# Peak_Detector.net
KiCad netlist of a schematic drawn in Altium Designer
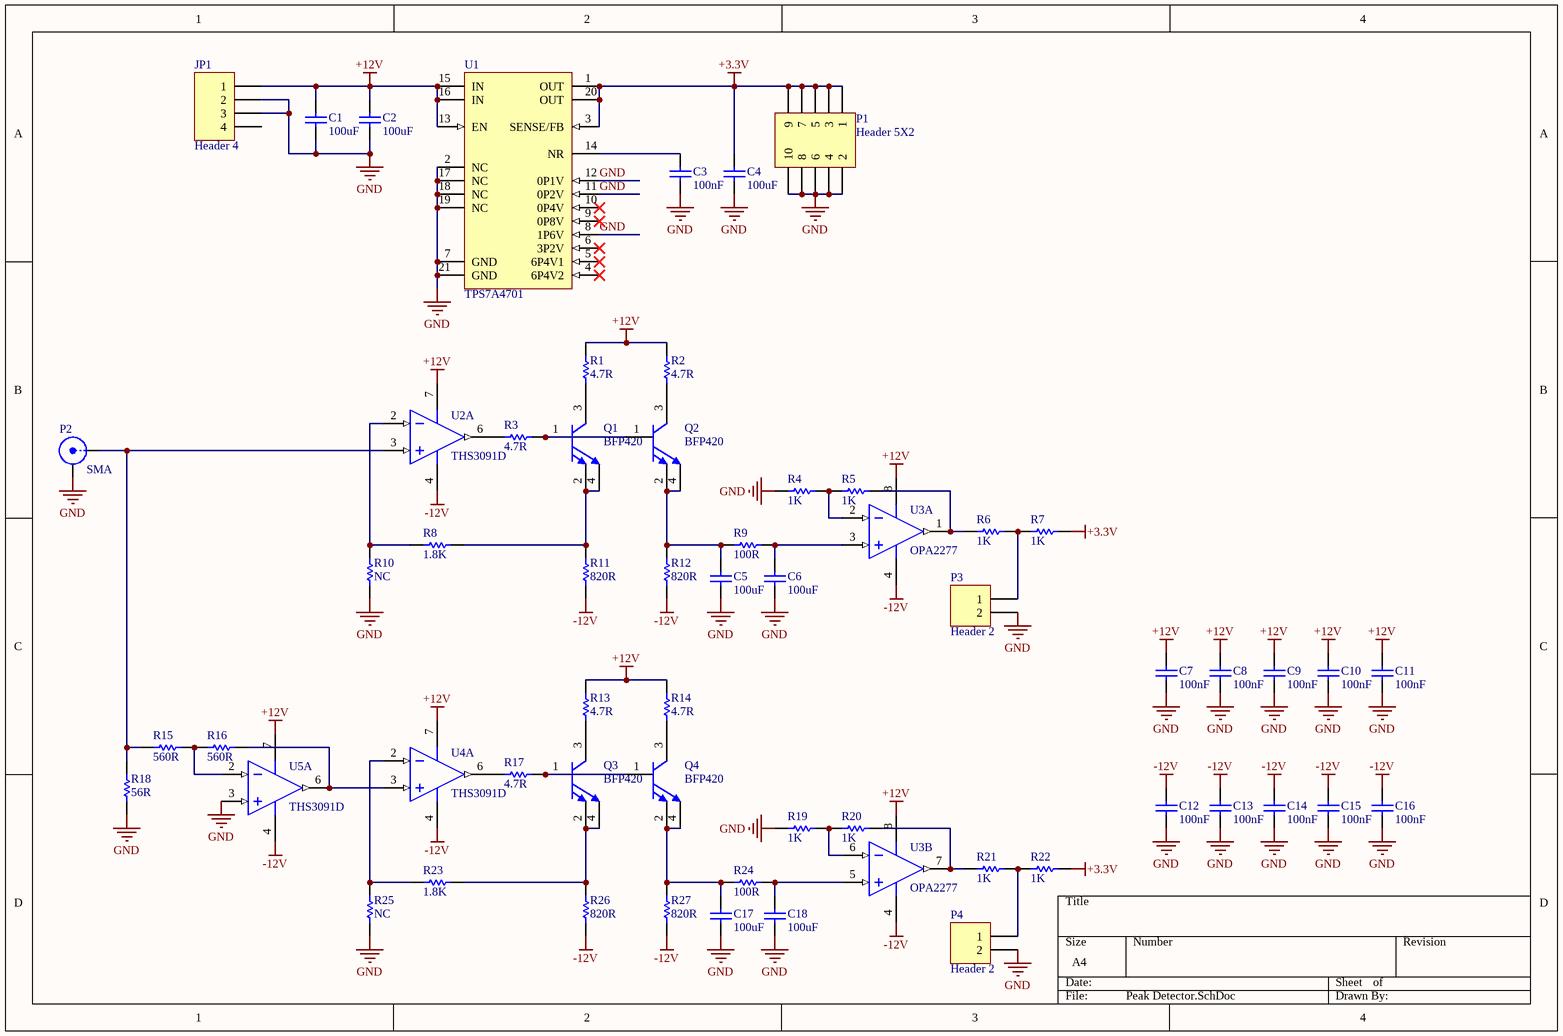
[diagram p0: Peak Detector.SchDoc]

(export (version "E")
  (design (tool "Eeschema 10.0.6"))
  (components
    (comp (ref "C1") (value "100uF") (footprint "CAPC3225") (libsource (lib "Slivy's Library") (part "CAP")))
    (comp (ref "C2") (value "100uF") (footprint "CAPC3225") (libsource (lib "Slivy's Library") (part "CAP")))
    (comp (ref "C3")
      (value "100nF")
      (footprint "CAPC0603(1608)55_M")
      (libsource (lib "Slivy's Library") (part "CAP"))
    )
    (comp (ref "C4") (value "100uF") (footprint "CAPC3225") (libsource (lib "Slivy's Library") (part "CAP")))
    (comp (ref "C5") (value "100uF") (footprint "CAPC3225") (libsource (lib "Slivy's Library") (part "CAP")))
    (comp (ref "C6") (value "100uF") (footprint "CAPC3225") (libsource (lib "Slivy's Library") (part "CAP")))
    (comp (ref "C7")
      (value "100nF")
      (footprint "CAPC0603(1608)55_M")
      (libsource (lib "Slivy's Library") (part "CAP"))
    )
    (comp (ref "C8")
      (value "100nF")
      (footprint "CAPC0603(1608)55_M")
      (libsource (lib "Slivy's Library") (part "CAP"))
    )
    (comp (ref "C9")
      (value "100nF")
      (footprint "CAPC0603(1608)55_M")
      (libsource (lib "Slivy's Library") (part "CAP"))
    )
    (comp (ref "C10")
      (value "100nF")
      (footprint "CAPC0603(1608)55_M")
      (libsource (lib "Slivy's Library") (part "CAP"))
    )
    (comp (ref "C11")
      (value "100nF")
      (footprint "CAPC0603(1608)55_M")
      (libsource (lib "Slivy's Library") (part "CAP"))
    )
    (comp (ref "C12")
      (value "100nF")
      (footprint "CAPC0603(1608)55_M")
      (libsource (lib "Slivy's Library") (part "CAP"))
    )
    (comp (ref "C13")
      (value "100nF")
      (footprint "CAPC0603(1608)55_M")
      (libsource (lib "Slivy's Library") (part "CAP"))
    )
    (comp (ref "C14")
      (value "100nF")
      (footprint "CAPC0603(1608)55_M")
      (libsource (lib "Slivy's Library") (part "CAP"))
    )
    (comp (ref "C15")
      (value "100nF")
      (footprint "CAPC0603(1608)55_M")
      (libsource (lib "Slivy's Library") (part "CAP"))
    )
    (comp (ref "C16")
      (value "100nF")
      (footprint "CAPC0603(1608)55_M")
      (libsource (lib "Slivy's Library") (part "CAP"))
    )
    (comp (ref "C17") (value "100uF") (footprint "CAPC3225") (libsource (lib "Slivy's Library") (part "CAP")))
    (comp (ref "C18") (value "100uF") (footprint "CAPC3225") (libsource (lib "Slivy's Library") (part "CAP")))
    (comp (ref "JP1")
      (value "Header 4")
      (footprint "3.96-4")
      (description "Header, 4-Pin")
      (fields (field (name "MANUFACTURER") "Generic Components"))
      (libsource (lib "Integrated_Library1") (part "Header 4"))
    )
    (comp (ref "P1")
      (value "Header 5X2")
      (footprint "HDR2X5")
      (description "Header, 5-Pin, Dual row")
      (fields (field (name "PUBLISHER") "Altium Limited"))
      (libsource (lib "Miscellaneous Connectors") (part "Header 5X2"))
    )
    (comp (ref "P2")
      (value "SMA")
      (footprint "SMA-V")
      (fields (field (name "PUBLISHER") "Altium Limited"))
      (libsource (lib "Slivy's Library") (part "SMA"))
    )
    (comp (ref "P3")
      (value "Header 2")
      (footprint "HDR1X2")
      (description "Header, 2-Pin")
      (fields (field (name "PUBLISHER") "Altium Limited"))
      (libsource (lib "Miscellaneous Connectors") (part "Header 2"))
    )
    (comp (ref "P4")
      (value "Header 2")
      (footprint "HDR1X2")
      (description "Header, 2-Pin")
      (fields (field (name "PUBLISHER") "Altium Limited"))
      (libsource (lib "Miscellaneous Connectors") (part "Header 2"))
    )
    (comp (ref "Q1")
      (value "BFP420")
      (footprint "SOT343")
      (libsource (lib "Slivy's Library") (part "BFP420"))
    )
    (comp (ref "Q2")
      (value "BFP420")
      (footprint "SOT343")
      (libsource (lib "Slivy's Library") (part "BFP420"))
    )
    (comp (ref "Q3")
      (value "BFP420")
      (footprint "SOT343")
      (libsource (lib "Slivy's Library") (part "BFP420"))
    )
    (comp (ref "Q4")
      (value "BFP420")
      (footprint "SOT343")
      (libsource (lib "Slivy's Library") (part "BFP420"))
    )
    (comp (ref "R1")
      (value "4.7R")
      (footprint "RESC0603(1608)_M")
      (libsource (lib "Slivy's Library") (part "RES"))
    )
    (comp (ref "R2")
      (value "4.7R")
      (footprint "RESC0603(1608)_M")
      (libsource (lib "Slivy's Library") (part "RES"))
    )
    (comp (ref "R3")
      (value "4.7R")
      (footprint "RESC0603(1608)_M")
      (libsource (lib "Slivy's Library") (part "RES"))
    )
    (comp (ref "R4")
      (value "1K")
      (footprint "RESC0603(1608)_M")
      (libsource (lib "Slivy's Library") (part "RES"))
    )
    (comp (ref "R5")
      (value "1K")
      (footprint "RESC0603(1608)_M")
      (libsource (lib "Slivy's Library") (part "RES"))
    )
    (comp (ref "R6")
      (value "1K")
      (footprint "RESC0603(1608)_M")
      (libsource (lib "Slivy's Library") (part "RES"))
    )
    (comp (ref "R7")
      (value "1K")
      (footprint "RESC0603(1608)_M")
      (libsource (lib "Slivy's Library") (part "RES"))
    )
    (comp (ref "R8")
      (value "1.8K")
      (footprint "RESC0603(1608)_M")
      (libsource (lib "Slivy's Library") (part "RES"))
    )
    (comp (ref "R9")
      (value "100R")
      (footprint "RESC0603(1608)_M")
      (libsource (lib "Slivy's Library") (part "RES"))
    )
    (comp (ref "R10")
      (value "NC")
      (footprint "RESC0603(1608)_M")
      (libsource (lib "Slivy's Library") (part "RES"))
    )
    (comp (ref "R11")
      (value "820R")
      (footprint "RESC0603(1608)_M")
      (libsource (lib "Slivy's Library") (part "RES"))
    )
    (comp (ref "R12")
      (value "820R")
      (footprint "RESC0603(1608)_M")
      (libsource (lib "Slivy's Library") (part "RES"))
    )
    (comp (ref "R13")
      (value "4.7R")
      (footprint "RESC0603(1608)_M")
      (libsource (lib "Slivy's Library") (part "RES"))
    )
    (comp (ref "R14")
      (value "4.7R")
      (footprint "RESC0603(1608)_M")
      (libsource (lib "Slivy's Library") (part "RES"))
    )
    (comp (ref "R15")
      (value "560R")
      (footprint "RESC0603(1608)_M")
      (libsource (lib "Slivy's Library") (part "RES"))
    )
    (comp (ref "R16")
      (value "560R")
      (footprint "RESC0603(1608)_M")
      (libsource (lib "Slivy's Library") (part "RES"))
    )
    (comp (ref "R17")
      (value "4.7R")
      (footprint "RESC0603(1608)_M")
      (libsource (lib "Slivy's Library") (part "RES"))
    )
    (comp (ref "R18")
      (value "56R")
      (footprint "RESC0603(1608)_M")
      (libsource (lib "Slivy's Library") (part "RES"))
    )
    (comp (ref "R19")
      (value "1K")
      (footprint "RESC0603(1608)_M")
      (libsource (lib "Slivy's Library") (part "RES"))
    )
    (comp (ref "R20")
      (value "1K")
      (footprint "RESC0603(1608)_M")
      (libsource (lib "Slivy's Library") (part "RES"))
    )
    (comp (ref "R21")
      (value "1K")
      (footprint "RESC0603(1608)_M")
      (libsource (lib "Slivy's Library") (part "RES"))
    )
    (comp (ref "R22")
      (value "1K")
      (footprint "RESC0603(1608)_M")
      (libsource (lib "Slivy's Library") (part "RES"))
    )
    (comp (ref "R23")
      (value "1.8K")
      (footprint "RESC0603(1608)_M")
      (libsource (lib "Slivy's Library") (part "RES"))
    )
    (comp (ref "R24")
      (value "100R")
      (footprint "RESC0603(1608)_M")
      (libsource (lib "Slivy's Library") (part "RES"))
    )
    (comp (ref "R25")
      (value "NC")
      (footprint "RESC0603(1608)_M")
      (libsource (lib "Slivy's Library") (part "RES"))
    )
    (comp (ref "R26")
      (value "820R")
      (footprint "RESC0603(1608)_M")
      (libsource (lib "Slivy's Library") (part "RES"))
    )
    (comp (ref "R27")
      (value "820R")
      (footprint "RESC0603(1608)_M")
      (libsource (lib "Slivy's Library") (part "RES"))
    )
    (comp (ref "U1")
      (value "TPS7A4701")
      (footprint "QFN20")
      (libsource (lib "Slivy's Library") (part "TPS7A4701"))
    )
    (comp (ref "U2")
      (value "THS3091D")
      (footprint "SOIC8")
      (libsource (lib "Slivy's Library") (part "THS3201"))
    )
    (comp (ref "U3") (value "OPA2277") (footprint "SOIC8") (libsource (lib "Slivy's Library") (part "OP2")))
    (comp (ref "U4")
      (value "THS3091D")
      (footprint "SOIC8")
      (libsource (lib "Slivy's Library") (part "THS3201"))
    )
    (comp (ref "U5")
      (value "THS3091D")
      (footprint "SOIC8")
      (libsource (lib "Slivy's Library") (part "THS3201"))
    )
  )
  (nets
    (net (code "1") (name "+3.3V") (class "Default")
      (node (ref "C4") (pin "2") (pinfunction "2_2") (pintype "passive"))
      (node (ref "P1") (pin "1") (pinfunction "1_1") (pintype "passive"))
      (node (ref "P1") (pin "3") (pinfunction "3_3") (pintype "passive"))
      (node (ref "P1") (pin "5") (pinfunction "5_5") (pintype "passive"))
      (node (ref "P1") (pin "7") (pinfunction "7_7") (pintype "passive"))
      (node (ref "P1") (pin "9") (pinfunction "9_9") (pintype "passive"))
      (node (ref "R22") (pin "1") (pinfunction "1_1") (pintype "passive"))
      (node (ref "R7") (pin "1") (pinfunction "1_1") (pintype "passive"))
      (node (ref "U1") (pin "1") (pinfunction "OUT_1") (pintype "power_in"))
      (node (ref "U1") (pin "20") (pinfunction "OUT_20") (pintype "power_in"))
      (node (ref "U1") (pin "3") (pinfunction "SENSE/FB_3") (pintype "input"))
    )
    (net (code "2") (name "+12V") (class "Default")
      (node (ref "C1") (pin "2") (pinfunction "2_2") (pintype "passive"))
      (node (ref "C10") (pin "2") (pinfunction "2_2") (pintype "passive"))
      (node (ref "C11") (pin "2") (pinfunction "2_2") (pintype "passive"))
      (node (ref "C2") (pin "2") (pinfunction "2_2") (pintype "passive"))
      (node (ref "C7") (pin "2") (pinfunction "2_2") (pintype "passive"))
      (node (ref "C8") (pin "2") (pinfunction "2_2") (pintype "passive"))
      (node (ref "C9") (pin "2") (pinfunction "2_2") (pintype "passive"))
      (node (ref "JP1") (pin "1") (pinfunction "1_1") (pintype "passive"))
      (node (ref "R1") (pin "2") (pinfunction "2_2") (pintype "passive"))
      (node (ref "R13") (pin "2") (pinfunction "2_2") (pintype "passive"))
      (node (ref "R14") (pin "2") (pinfunction "2_2") (pintype "passive"))
      (node (ref "R2") (pin "2") (pinfunction "2_2") (pintype "passive"))
      (node (ref "U1") (pin "13") (pinfunction "EN_13") (pintype "input"))
      (node (ref "U1") (pin "15") (pinfunction "IN_15") (pintype "power_in"))
      (node (ref "U1") (pin "16") (pinfunction "IN_16") (pintype "power_in"))
      (node (ref "U2") (pin "7") (pinfunction "VS+_7") (pintype "power_in"))
      (node (ref "U3") (pin "8") (pinfunction "V+_8") (pintype "power_in"))
      (node (ref "U4") (pin "7") (pinfunction "VS+_7") (pintype "power_in"))
      (node (ref "U5") (pin "7") (pinfunction "VS+_7") (pintype "power_in"))
    )
    (net (code "3") (name "-12V") (class "Default")
      (node (ref "C12") (pin "2") (pinfunction "2_2") (pintype "passive"))
      (node (ref "C13") (pin "2") (pinfunction "2_2") (pintype "passive"))
      (node (ref "C14") (pin "2") (pinfunction "2_2") (pintype "passive"))
      (node (ref "C15") (pin "2") (pinfunction "2_2") (pintype "passive"))
      (node (ref "C16") (pin "2") (pinfunction "2_2") (pintype "passive"))
      (node (ref "R11") (pin "1") (pinfunction "1_1") (pintype "passive"))
      (node (ref "R12") (pin "1") (pinfunction "1_1") (pintype "passive"))
      (node (ref "R26") (pin "1") (pinfunction "1_1") (pintype "passive"))
      (node (ref "R27") (pin "1") (pinfunction "1_1") (pintype "passive"))
      (node (ref "U2") (pin "4") (pinfunction "VS-_4") (pintype "power_in"))
      (node (ref "U3") (pin "4") (pinfunction "V-_4") (pintype "power_in"))
      (node (ref "U4") (pin "4") (pinfunction "VS-_4") (pintype "power_in"))
      (node (ref "U5") (pin "4") (pinfunction "VS-_4") (pintype "power_in"))
    )
    (net (code "4") (name "GND") (class "Default")
      (node (ref "C1") (pin "1") (pinfunction "1_1") (pintype "passive"))
      (node (ref "C10") (pin "1") (pinfunction "1_1") (pintype "passive"))
      (node (ref "C11") (pin "1") (pinfunction "1_1") (pintype "passive"))
      (node (ref "C12") (pin "1") (pinfunction "1_1") (pintype "passive"))
      (node (ref "C13") (pin "1") (pinfunction "1_1") (pintype "passive"))
      (node (ref "C14") (pin "1") (pinfunction "1_1") (pintype "passive"))
      (node (ref "C15") (pin "1") (pinfunction "1_1") (pintype "passive"))
      (node (ref "C16") (pin "1") (pinfunction "1_1") (pintype "passive"))
      (node (ref "C17") (pin "1") (pinfunction "1_1") (pintype "passive"))
      (node (ref "C18") (pin "1") (pinfunction "1_1") (pintype "passive"))
      (node (ref "C2") (pin "1") (pinfunction "1_1") (pintype "passive"))
      (node (ref "C3") (pin "1") (pinfunction "1_1") (pintype "passive"))
      (node (ref "C4") (pin "1") (pinfunction "1_1") (pintype "passive"))
      (node (ref "C5") (pin "1") (pinfunction "1_1") (pintype "passive"))
      (node (ref "C6") (pin "1") (pinfunction "1_1") (pintype "passive"))
      (node (ref "C7") (pin "1") (pinfunction "1_1") (pintype "passive"))
      (node (ref "C8") (pin "1") (pinfunction "1_1") (pintype "passive"))
      (node (ref "C9") (pin "1") (pinfunction "1_1") (pintype "passive"))
      (node (ref "JP1") (pin "2") (pinfunction "2_2") (pintype "passive"))
      (node (ref "JP1") (pin "3") (pinfunction "3_3") (pintype "passive"))
      (node (ref "P1") (pin "10") (pinfunction "10_10") (pintype "passive"))
      (node (ref "P1") (pin "2") (pinfunction "2_2") (pintype "passive"))
      (node (ref "P1") (pin "4") (pinfunction "4_4") (pintype "passive"))
      (node (ref "P1") (pin "6") (pinfunction "6_6") (pintype "passive"))
      (node (ref "P1") (pin "8") (pinfunction "8_8") (pintype "passive"))
      (node (ref "P2") (pin "2") (pinfunction "Y_2") (pintype "passive"))
      (node (ref "P3") (pin "2") (pinfunction "2_2") (pintype "passive"))
      (node (ref "P4") (pin "2") (pinfunction "2_2") (pintype "passive"))
      (node (ref "R10") (pin "2") (pinfunction "2_2") (pintype "passive"))
      (node (ref "R18") (pin "2") (pinfunction "2_2") (pintype "passive"))
      (node (ref "R19") (pin "2") (pinfunction "2_2") (pintype "passive"))
      (node (ref "R25") (pin "2") (pinfunction "2_2") (pintype "passive"))
      (node (ref "R4") (pin "2") (pinfunction "2_2") (pintype "passive"))
      (node (ref "U1") (pin "11") (pinfunction "0P2V_11") (pintype "input"))
      (node (ref "U1") (pin "12") (pinfunction "0P1V_12") (pintype "input"))
      (node (ref "U1") (pin "17") (pinfunction "NC_17") (pintype "passive"))
      (node (ref "U1") (pin "18") (pinfunction "NC_18") (pintype "passive"))
      (node (ref "U1") (pin "19") (pinfunction "NC_19") (pintype "passive"))
      (node (ref "U1") (pin "2") (pinfunction "NC_2") (pintype "passive"))
      (node (ref "U1") (pin "21") (pinfunction "GND_21") (pintype "power_in"))
      (node (ref "U1") (pin "7") (pinfunction "GND_7") (pintype "power_in"))
      (node (ref "U1") (pin "8") (pinfunction "1P6V_8") (pintype "input"))
      (node (ref "U5") (pin "3") (pinfunction "VIN+_3") (pintype "input"))
    )
    (net (code "5") (name "Net-(C5-Pad2)") (class "Default")
      (node (ref "C5") (pin "2") (pinfunction "2_2") (pintype "passive"))
      (node (ref "Q2") (pin "2") (pinfunction "E_2") (pintype "passive"))
      (node (ref "Q2") (pin "4") (pinfunction "E_4") (pintype "passive"))
      (node (ref "R12") (pin "2") (pinfunction "2_2") (pintype "passive"))
      (node (ref "R9") (pin "2") (pinfunction "2_2") (pintype "passive"))
    )
    (net (code "6") (name "Net-(C17-Pad2)") (class "Default")
      (node (ref "C17") (pin "2") (pinfunction "2_2") (pintype "passive"))
      (node (ref "Q4") (pin "2") (pinfunction "E_2") (pintype "passive"))
      (node (ref "Q4") (pin "4") (pinfunction "E_4") (pintype "passive"))
      (node (ref "R24") (pin "2") (pinfunction "2_2") (pintype "passive"))
      (node (ref "R27") (pin "2") (pinfunction "2_2") (pintype "passive"))
    )
    (net (code "7") (name "Net-(P2-X)") (class "Default")
      (node (ref "P2") (pin "1") (pinfunction "X_1") (pintype "passive"))
      (node (ref "R15") (pin "2") (pinfunction "2_2") (pintype "passive"))
      (node (ref "R18") (pin "1") (pinfunction "1_1") (pintype "passive"))
      (node (ref "U2") (pin "3") (pinfunction "VIN+_3") (pintype "input"))
    )
    (net (code "8") (name "Net-(P3-Pad1)") (class "Default")
      (node (ref "P3") (pin "1") (pinfunction "1_1") (pintype "passive"))
      (node (ref "R6") (pin "1") (pinfunction "1_1") (pintype "passive"))
      (node (ref "R7") (pin "2") (pinfunction "2_2") (pintype "passive"))
    )
    (net (code "9") (name "Net-(P4-Pad1)") (class "Default")
      (node (ref "P4") (pin "1") (pinfunction "1_1") (pintype "passive"))
      (node (ref "R21") (pin "1") (pinfunction "1_1") (pintype "passive"))
      (node (ref "R22") (pin "2") (pinfunction "2_2") (pintype "passive"))
    )
    (net (code "10") (name "Net-(Q1-B)") (class "Default")
      (node (ref "Q1") (pin "1") (pinfunction "B_1") (pintype "passive"))
      (node (ref "Q2") (pin "1") (pinfunction "B_1") (pintype "passive"))
      (node (ref "R3") (pin "1") (pinfunction "1_1") (pintype "passive"))
    )
    (net (code "11") (name "Net-(Q1-C)") (class "Default")
      (node (ref "Q1") (pin "3") (pinfunction "C_3") (pintype "passive"))
      (node (ref "R1") (pin "1") (pinfunction "1_1") (pintype "passive"))
    )
    (net (code "12") (name "Net-(Q1-E-Pad2)") (class "Default")
      (node (ref "Q1") (pin "2") (pinfunction "E_2") (pintype "passive"))
      (node (ref "Q1") (pin "4") (pinfunction "E_4") (pintype "passive"))
      (node (ref "R11") (pin "2") (pinfunction "2_2") (pintype "passive"))
      (node (ref "R8") (pin "1") (pinfunction "1_1") (pintype "passive"))
    )
    (net (code "13") (name "Net-(Q2-C)") (class "Default")
      (node (ref "Q2") (pin "3") (pinfunction "C_3") (pintype "passive"))
      (node (ref "R2") (pin "1") (pinfunction "1_1") (pintype "passive"))
    )
    (net (code "14") (name "Net-(Q3-B)") (class "Default")
      (node (ref "Q3") (pin "1") (pinfunction "B_1") (pintype "passive"))
      (node (ref "Q4") (pin "1") (pinfunction "B_1") (pintype "passive"))
      (node (ref "R17") (pin "1") (pinfunction "1_1") (pintype "passive"))
    )
    (net (code "15") (name "Net-(Q3-C)") (class "Default")
      (node (ref "Q3") (pin "3") (pinfunction "C_3") (pintype "passive"))
      (node (ref "R13") (pin "1") (pinfunction "1_1") (pintype "passive"))
    )
    (net (code "16") (name "Net-(Q3-E-Pad2)") (class "Default")
      (node (ref "Q3") (pin "2") (pinfunction "E_2") (pintype "passive"))
      (node (ref "Q3") (pin "4") (pinfunction "E_4") (pintype "passive"))
      (node (ref "R23") (pin "1") (pinfunction "1_1") (pintype "passive"))
      (node (ref "R26") (pin "2") (pinfunction "2_2") (pintype "passive"))
    )
    (net (code "17") (name "Net-(Q4-C)") (class "Default")
      (node (ref "Q4") (pin "3") (pinfunction "C_3") (pintype "passive"))
      (node (ref "R14") (pin "1") (pinfunction "1_1") (pintype "passive"))
    )
    (net (code "18") (name "Net-(U1-NR)") (class "Default")
      (node (ref "C3") (pin "2") (pinfunction "2_2") (pintype "passive"))
      (node (ref "U1") (pin "14") (pinfunction "NR_14") (pintype "passive"))
    )
    (net (code "19") (name "Net-(U2A-VIN-)") (class "Default")
      (node (ref "R10") (pin "1") (pinfunction "1_1") (pintype "passive"))
      (node (ref "R8") (pin "2") (pinfunction "2_2") (pintype "passive"))
      (node (ref "U2") (pin "2") (pinfunction "VIN-_2") (pintype "input"))
    )
    (net (code "20") (name "Net-(U2A-VOUT)") (class "Default")
      (node (ref "R3") (pin "2") (pinfunction "2_2") (pintype "passive"))
      (node (ref "U2") (pin "6") (pinfunction "VOUT_6") (pintype "output"))
    )
    (net (code "21") (name "Net-(U3A-IN_A+)") (class "Default")
      (node (ref "C6") (pin "2") (pinfunction "2_2") (pintype "passive"))
      (node (ref "R9") (pin "1") (pinfunction "1_1") (pintype "passive"))
      (node (ref "U3") (pin "3") (pinfunction "IN_A+_3") (pintype "input"))
    )
    (net (code "22") (name "Net-(U3A-IN_A-)") (class "Default")
      (node (ref "R4") (pin "1") (pinfunction "1_1") (pintype "passive"))
      (node (ref "R5") (pin "2") (pinfunction "2_2") (pintype "passive"))
      (node (ref "U3") (pin "2") (pinfunction "IN_A-_2") (pintype "input"))
    )
    (net (code "23") (name "Net-(U3A-OUT_A)") (class "Default")
      (node (ref "R5") (pin "1") (pinfunction "1_1") (pintype "passive"))
      (node (ref "R6") (pin "2") (pinfunction "2_2") (pintype "passive"))
      (node (ref "U3") (pin "1") (pinfunction "OUT_A_1") (pintype "output"))
    )
    (net (code "24") (name "Net-(U3B-IN_B+)") (class "Default")
      (node (ref "C18") (pin "2") (pinfunction "2_2") (pintype "passive"))
      (node (ref "R24") (pin "1") (pinfunction "1_1") (pintype "passive"))
      (node (ref "U3") (pin "5") (pinfunction "IN_B+_5") (pintype "input"))
    )
    (net (code "25") (name "Net-(U3B-IN_B-)") (class "Default")
      (node (ref "R19") (pin "1") (pinfunction "1_1") (pintype "passive"))
      (node (ref "R20") (pin "2") (pinfunction "2_2") (pintype "passive"))
      (node (ref "U3") (pin "6") (pinfunction "IN_B-_6") (pintype "input"))
    )
    (net (code "26") (name "Net-(U3B-OUT_B)") (class "Default")
      (node (ref "R20") (pin "1") (pinfunction "1_1") (pintype "passive"))
      (node (ref "R21") (pin "2") (pinfunction "2_2") (pintype "passive"))
      (node (ref "U3") (pin "7") (pinfunction "OUT_B_7") (pintype "output"))
    )
    (net (code "27") (name "Net-(U4A-VIN+)") (class "Default")
      (node (ref "R16") (pin "1") (pinfunction "1_1") (pintype "passive"))
      (node (ref "U4") (pin "3") (pinfunction "VIN+_3") (pintype "input"))
      (node (ref "U5") (pin "6") (pinfunction "VOUT_6") (pintype "output"))
    )
    (net (code "28") (name "Net-(U4A-VIN-)") (class "Default")
      (node (ref "R23") (pin "2") (pinfunction "2_2") (pintype "passive"))
      (node (ref "R25") (pin "1") (pinfunction "1_1") (pintype "passive"))
      (node (ref "U4") (pin "2") (pinfunction "VIN-_2") (pintype "input"))
    )
    (net (code "29") (name "Net-(U4A-VOUT)") (class "Default")
      (node (ref "R17") (pin "2") (pinfunction "2_2") (pintype "passive"))
      (node (ref "U4") (pin "6") (pinfunction "VOUT_6") (pintype "output"))
    )
    (net (code "30") (name "Net-(U5A-VIN-)") (class "Default")
      (node (ref "R15") (pin "1") (pinfunction "1_1") (pintype "passive"))
      (node (ref "R16") (pin "2") (pinfunction "2_2") (pintype "passive"))
      (node (ref "U5") (pin "2") (pinfunction "VIN-_2") (pintype "input"))
    )
    (net (code "31") (name "unconnected-(JP1-Pad4)") (class "Default")
      (node (ref "JP1") (pin "4") (pinfunction "4_4") (pintype "passive"))
    )
    (net (code "32") (name "unconnected-(U1-0P4V-Pad10)") (class "Default")
      (node (ref "U1") (pin "10") (pinfunction "0P4V_10") (pintype "input+no_connect"))
    )
    (net (code "33") (name "unconnected-(U1-0P8V-Pad9)") (class "Default")
      (node (ref "U1") (pin "9") (pinfunction "0P8V_9") (pintype "input+no_connect"))
    )
    (net (code "34") (name "unconnected-(U1-3P2V-Pad6)") (class "Default")
      (node (ref "U1") (pin "6") (pinfunction "3P2V_6") (pintype "input+no_connect"))
    )
    (net (code "35") (name "unconnected-(U1-6P4V1-Pad5)") (class "Default")
      (node (ref "U1") (pin "5") (pinfunction "6P4V1_5") (pintype "input+no_connect"))
    )
    (net (code "36") (name "unconnected-(U1-6P4V2-Pad4)") (class "Default")
      (node (ref "U1") (pin "4") (pinfunction "6P4V2_4") (pintype "input+no_connect"))
    )
  )
)
